# valve_board-OSH.net
KiCad netlist of a schematic drawn in EAGLE
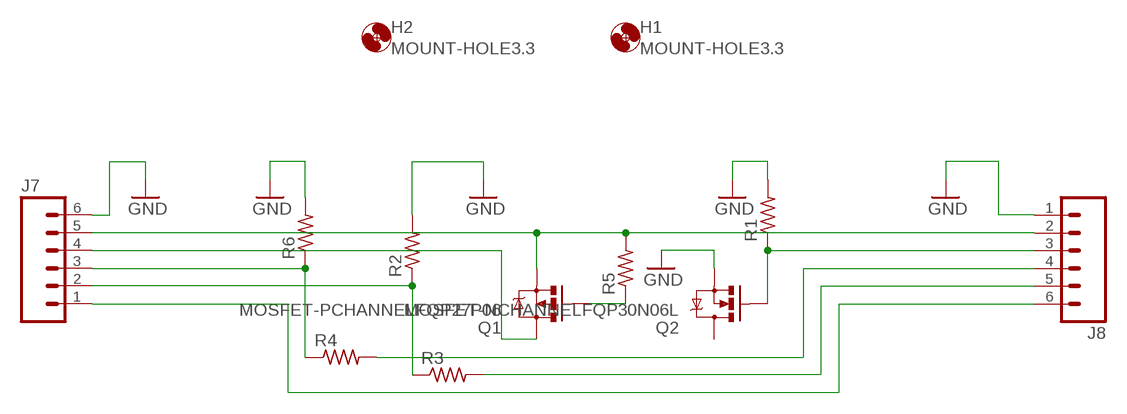
[diagram p0: schematic, sheet 1]

(export (version "E")
  (design (tool "Eeschema 10.0.6"))
  (components
    (comp (ref "H1")
      (value "MOUNT-HOLE3.3")
      (footprint "eagle-import:3,3")
      (libsource (lib "eagle-import") (part "MOUNT-HOLE3.3"))
    )
    (comp (ref "H2")
      (value "MOUNT-HOLE3.3")
      (footprint "eagle-import:3,3")
      (libsource (lib "eagle-import") (part "MOUNT-HOLE3.3"))
    )
    (comp (ref "J7")
      (value "M06LOCK_LONGPADS")
      (footprint "eagle-import:1X06_LOCK_LONGPADS")
      (libsource (lib "eagle-import") (part "M06LOCK_LONGPADS"))
    )
    (comp (ref "J8")
      (value "M06LOCK_LONGPADS")
      (footprint "eagle-import:1X06_LOCK_LONGPADS")
      (libsource (lib "eagle-import") (part "M06LOCK_LONGPADS"))
    )
    (comp (ref "Q1")
      (value "MOSFET-PCHANNELFQP27P06")
      (footprint "eagle-import:TO220V")
      (libsource (lib "eagle-import") (part "MOSFET-PCHANNELFQP27P06"))
    )
    (comp (ref "Q2")
      (value "MOSFET-NCHANNELFQP30N06L")
      (footprint "eagle-import:TO220V")
      (libsource (lib "eagle-import") (part "MOSFET-NCHANNELFQP30N06L"))
    )
    (comp (ref "R1")
      (value "R-US_0207/10")
      (footprint "eagle-import:0207_10")
      (libsource (lib "eagle-import") (part "R-US_0207/10"))
    )
    (comp (ref "R2")
      (value "R-US_0207/10")
      (footprint "eagle-import:0207_10")
      (libsource (lib "eagle-import") (part "R-US_0207/10"))
    )
    (comp (ref "R3")
      (value "R-US_0207/10")
      (footprint "eagle-import:0207_10")
      (libsource (lib "eagle-import") (part "R-US_0207/10"))
    )
    (comp (ref "R4")
      (value "R-US_0207/10")
      (footprint "eagle-import:0207_10")
      (libsource (lib "eagle-import") (part "R-US_0207/10"))
    )
    (comp (ref "R5")
      (value "R-US_0207/10")
      (footprint "eagle-import:0207_10")
      (libsource (lib "eagle-import") (part "R-US_0207/10"))
    )
    (comp (ref "R6")
      (value "R-US_0207/10")
      (footprint "eagle-import:0207_10")
      (libsource (lib "eagle-import") (part "R-US_0207/10"))
    )
  )
  (nets
    (net (code "1") (name "GND") (class "Default")
      (node (ref "J7") (pin "6") (pinfunction "6_6") (pintype "passive"))
      (node (ref "J8") (pin "1") (pinfunction "1_1") (pintype "passive"))
      (node (ref "Q2") (pin "3") (pinfunction "S_3") (pintype "passive"))
      (node (ref "R1") (pin "2") (pinfunction "2_2") (pintype "passive"))
      (node (ref "R2") (pin "2") (pinfunction "2_2") (pintype "passive"))
      (node (ref "R6") (pin "2") (pinfunction "2_2") (pintype "passive"))
    )
    (net (code "2") (name "Net-(J7-Pad1)") (class "Default")
      (node (ref "J7") (pin "1") (pinfunction "1_1") (pintype "passive"))
      (node (ref "J8") (pin "6") (pinfunction "6_6") (pintype "passive"))
    )
    (net (code "3") (name "Net-(J7-Pad2)") (class "Default")
      (node (ref "J7") (pin "2") (pinfunction "2_2") (pintype "passive"))
      (node (ref "R2") (pin "1") (pinfunction "1_1") (pintype "passive"))
      (node (ref "R3") (pin "1") (pinfunction "1_1") (pintype "passive"))
    )
    (net (code "4") (name "Net-(J7-Pad3)") (class "Default")
      (node (ref "J7") (pin "3") (pinfunction "3_3") (pintype "passive"))
      (node (ref "R4") (pin "1") (pinfunction "1_1") (pintype "passive"))
      (node (ref "R6") (pin "1") (pinfunction "1_1") (pintype "passive"))
    )
    (net (code "5") (name "Net-(J8-Pad4)") (class "Default")
      (node (ref "J8") (pin "4") (pinfunction "4_4") (pintype "passive"))
      (node (ref "R4") (pin "2") (pinfunction "2_2") (pintype "passive"))
    )
    (net (code "6") (name "Net-(J8-Pad5)") (class "Default")
      (node (ref "J8") (pin "5") (pinfunction "5_5") (pintype "passive"))
      (node (ref "R3") (pin "2") (pinfunction "2_2") (pintype "passive"))
    )
    (net (code "7") (name "Net-(Q1-D)") (class "Default")
      (node (ref "J7") (pin "4") (pinfunction "4_4") (pintype "passive"))
      (node (ref "Q1") (pin "2") (pinfunction "D_2") (pintype "passive"))
    )
    (net (code "8") (name "Net-(Q1-G)") (class "Default")
      (node (ref "Q1") (pin "1") (pinfunction "G_1") (pintype "passive"))
      (node (ref "R5") (pin "1") (pinfunction "1_1") (pintype "passive"))
    )
    (net (code "9") (name "Net-(Q1-S)") (class "Default")
      (node (ref "J7") (pin "5") (pinfunction "5_5") (pintype "passive"))
      (node (ref "J8") (pin "2") (pinfunction "2_2") (pintype "passive"))
      (node (ref "Q1") (pin "3") (pinfunction "S_3") (pintype "passive"))
      (node (ref "R5") (pin "2") (pinfunction "2_2") (pintype "passive"))
    )
    (net (code "10") (name "Net-(Q2-G)") (class "Default")
      (node (ref "J8") (pin "3") (pinfunction "3_3") (pintype "passive"))
      (node (ref "Q2") (pin "1") (pinfunction "G_1") (pintype "passive"))
      (node (ref "R1") (pin "1") (pinfunction "1_1") (pintype "passive"))
    )
    (net (code "11") (name "unconnected-(Q2-D-Pad2)") (class "Default")
      (node (ref "Q2") (pin "2") (pinfunction "D_2") (pintype "passive"))
    )
  )
)
